# IcosaCharlieCylon.net
KiCad netlist of a schematic drawn in EAGLE
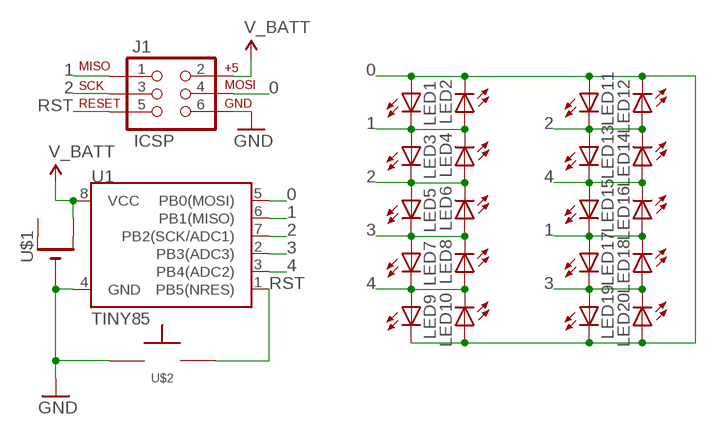
[diagram p0: schematic, sheet 1]

(export (version "E")
  (design (tool "Eeschema 10.0.6"))
  (components
    (comp (ref "J1")
      (value "ICSP")
      (footprint "eagle-import:2X3-NS")
      (libsource (lib "eagle-import") (part "AVR_SPI_PRG_6LABELED"))
    )
    (comp (ref "LED1")
      (value "LEDOVAL")
      (footprint "eagle-import:LED-OVAL")
      (libsource (lib "eagle-import") (part "LEDOVAL"))
    )
    (comp (ref "LED2")
      (value "LEDOVAL")
      (footprint "eagle-import:LED-OVAL")
      (libsource (lib "eagle-import") (part "LEDOVAL"))
    )
    (comp (ref "LED3")
      (value "LEDOVAL")
      (footprint "eagle-import:LED-OVAL")
      (libsource (lib "eagle-import") (part "LEDOVAL"))
    )
    (comp (ref "LED4")
      (value "LEDOVAL")
      (footprint "eagle-import:LED-OVAL")
      (libsource (lib "eagle-import") (part "LEDOVAL"))
    )
    (comp (ref "LED5")
      (value "LEDOVAL")
      (footprint "eagle-import:LED-OVAL")
      (libsource (lib "eagle-import") (part "LEDOVAL"))
    )
    (comp (ref "LED6")
      (value "LEDOVAL")
      (footprint "eagle-import:LED-OVAL")
      (libsource (lib "eagle-import") (part "LEDOVAL"))
    )
    (comp (ref "LED7")
      (value "LEDOVAL")
      (footprint "eagle-import:LED-OVAL")
      (libsource (lib "eagle-import") (part "LEDOVAL"))
    )
    (comp (ref "LED8")
      (value "LEDOVAL")
      (footprint "eagle-import:LED-OVAL")
      (libsource (lib "eagle-import") (part "LEDOVAL"))
    )
    (comp (ref "LED9")
      (value "LEDOVAL")
      (footprint "eagle-import:LED-OVAL")
      (libsource (lib "eagle-import") (part "LEDOVAL"))
    )
    (comp (ref "LED10")
      (value "LEDOVAL")
      (footprint "eagle-import:LED-OVAL")
      (libsource (lib "eagle-import") (part "LEDOVAL"))
    )
    (comp (ref "LED11")
      (value "LEDOVAL")
      (footprint "eagle-import:LED-OVAL")
      (libsource (lib "eagle-import") (part "LEDOVAL"))
    )
    (comp (ref "LED12")
      (value "LEDOVAL")
      (footprint "eagle-import:LED-OVAL")
      (libsource (lib "eagle-import") (part "LEDOVAL"))
    )
    (comp (ref "LED13")
      (value "LEDOVAL")
      (footprint "eagle-import:LED-OVAL")
      (libsource (lib "eagle-import") (part "LEDOVAL"))
    )
    (comp (ref "LED14")
      (value "LEDOVAL")
      (footprint "eagle-import:LED-OVAL")
      (libsource (lib "eagle-import") (part "LEDOVAL"))
    )
    (comp (ref "LED15")
      (value "LEDOVAL")
      (footprint "eagle-import:LED-OVAL")
      (libsource (lib "eagle-import") (part "LEDOVAL"))
    )
    (comp (ref "LED16")
      (value "LEDOVAL")
      (footprint "eagle-import:LED-OVAL")
      (libsource (lib "eagle-import") (part "LEDOVAL"))
    )
    (comp (ref "LED17")
      (value "LEDOVAL")
      (footprint "eagle-import:LED-OVAL")
      (libsource (lib "eagle-import") (part "LEDOVAL"))
    )
    (comp (ref "LED18")
      (value "LEDOVAL")
      (footprint "eagle-import:LED-OVAL")
      (libsource (lib "eagle-import") (part "LEDOVAL"))
    )
    (comp (ref "LED19")
      (value "LEDOVAL")
      (footprint "eagle-import:LED-OVAL")
      (libsource (lib "eagle-import") (part "LEDOVAL"))
    )
    (comp (ref "LED20")
      (value "LEDOVAL")
      (footprint "eagle-import:LED-OVAL")
      (libsource (lib "eagle-import") (part "LEDOVAL"))
    )
    (comp (ref "U$1")
      (value "CR2032THM")
      (footprint "eagle-import:CR2032-THRU")
      (libsource (lib "eagle-import") (part "CR2032THM"))
    )
    (comp (ref "U$2")
      (value "TAC_SPST_NO")
      (footprint "eagle-import:TAC_SPST_NO")
      (libsource (lib "eagle-import") (part "TAC_SPST_NO"))
    )
    (comp (ref "U1")
      (value "TINY85")
      (footprint "eagle-import:DIP08")
      (libsource (lib "eagle-import") (part "ATTINY45TINY85-20-DIP"))
    )
  )
  (nets
    (net (code "1") (name "/0") (class "Default")
      (node (ref "J1") (pin "4") (pinfunction "MOSI_4") (pintype "passive"))
      (node (ref "LED1") (pin "ANODE") (pinfunction "A_ANODE") (pintype "passive"))
      (node (ref "LED10") (pin "ANODE") (pinfunction "A_ANODE") (pintype "passive"))
      (node (ref "LED11") (pin "ANODE") (pinfunction "A_ANODE") (pintype "passive"))
      (node (ref "LED12") (pin "CATHODE") (pinfunction "C_CATHODE") (pintype "passive"))
      (node (ref "LED19") (pin "CATHODE") (pinfunction "C_CATHODE") (pintype "passive"))
      (node (ref "LED2") (pin "CATHODE") (pinfunction "C_CATHODE") (pintype "passive"))
      (node (ref "LED20") (pin "ANODE") (pinfunction "A_ANODE") (pintype "passive"))
      (node (ref "LED9") (pin "CATHODE") (pinfunction "C_CATHODE") (pintype "passive"))
      (node (ref "U1") (pin "5") (pinfunction "PB0(MOSI)_5") (pintype "bidirectional"))
    )
    (net (code "2") (name "/1") (class "Default")
      (node (ref "J1") (pin "1") (pinfunction "MISO_1") (pintype "passive"))
      (node (ref "LED1") (pin "CATHODE") (pinfunction "C_CATHODE") (pintype "passive"))
      (node (ref "LED15") (pin "CATHODE") (pinfunction "C_CATHODE") (pintype "passive"))
      (node (ref "LED16") (pin "ANODE") (pinfunction "A_ANODE") (pintype "passive"))
      (node (ref "LED17") (pin "ANODE") (pinfunction "A_ANODE") (pintype "passive"))
      (node (ref "LED18") (pin "CATHODE") (pinfunction "C_CATHODE") (pintype "passive"))
      (node (ref "LED2") (pin "ANODE") (pinfunction "A_ANODE") (pintype "passive"))
      (node (ref "LED3") (pin "ANODE") (pinfunction "A_ANODE") (pintype "passive"))
      (node (ref "LED4") (pin "CATHODE") (pinfunction "C_CATHODE") (pintype "passive"))
      (node (ref "U1") (pin "6") (pinfunction "PB1(MISO)_6") (pintype "bidirectional"))
    )
    (net (code "3") (name "/2") (class "Default")
      (node (ref "J1") (pin "3") (pinfunction "SCK_3") (pintype "passive"))
      (node (ref "LED11") (pin "CATHODE") (pinfunction "C_CATHODE") (pintype "passive"))
      (node (ref "LED12") (pin "ANODE") (pinfunction "A_ANODE") (pintype "passive"))
      (node (ref "LED13") (pin "ANODE") (pinfunction "A_ANODE") (pintype "passive"))
      (node (ref "LED14") (pin "CATHODE") (pinfunction "C_CATHODE") (pintype "passive"))
      (node (ref "LED3") (pin "CATHODE") (pinfunction "C_CATHODE") (pintype "passive"))
      (node (ref "LED4") (pin "ANODE") (pinfunction "A_ANODE") (pintype "passive"))
      (node (ref "LED5") (pin "ANODE") (pinfunction "A_ANODE") (pintype "passive"))
      (node (ref "LED6") (pin "CATHODE") (pinfunction "C_CATHODE") (pintype "passive"))
      (node (ref "U1") (pin "7") (pinfunction "PB2(SCK/ADC1)_7") (pintype "bidirectional"))
    )
    (net (code "4") (name "/3") (class "Default")
      (node (ref "LED17") (pin "CATHODE") (pinfunction "C_CATHODE") (pintype "passive"))
      (node (ref "LED18") (pin "ANODE") (pinfunction "A_ANODE") (pintype "passive"))
      (node (ref "LED19") (pin "ANODE") (pinfunction "A_ANODE") (pintype "passive"))
      (node (ref "LED20") (pin "CATHODE") (pinfunction "C_CATHODE") (pintype "passive"))
      (node (ref "LED5") (pin "CATHODE") (pinfunction "C_CATHODE") (pintype "passive"))
      (node (ref "LED6") (pin "ANODE") (pinfunction "A_ANODE") (pintype "passive"))
      (node (ref "LED7") (pin "ANODE") (pinfunction "A_ANODE") (pintype "passive"))
      (node (ref "LED8") (pin "CATHODE") (pinfunction "C_CATHODE") (pintype "passive"))
      (node (ref "U1") (pin "2") (pinfunction "PB3(ADC3)_2") (pintype "bidirectional"))
    )
    (net (code "5") (name "/4") (class "Default")
      (node (ref "LED10") (pin "CATHODE") (pinfunction "C_CATHODE") (pintype "passive"))
      (node (ref "LED13") (pin "CATHODE") (pinfunction "C_CATHODE") (pintype "passive"))
      (node (ref "LED14") (pin "ANODE") (pinfunction "A_ANODE") (pintype "passive"))
      (node (ref "LED15") (pin "ANODE") (pinfunction "A_ANODE") (pintype "passive"))
      (node (ref "LED16") (pin "CATHODE") (pinfunction "C_CATHODE") (pintype "passive"))
      (node (ref "LED7") (pin "CATHODE") (pinfunction "C_CATHODE") (pintype "passive"))
      (node (ref "LED8") (pin "ANODE") (pinfunction "A_ANODE") (pintype "passive"))
      (node (ref "LED9") (pin "ANODE") (pinfunction "A_ANODE") (pintype "passive"))
      (node (ref "U1") (pin "3") (pinfunction "PB4(ADC2)_3") (pintype "bidirectional"))
    )
    (net (code "6") (name "/RST") (class "Default")
      (node (ref "J1") (pin "5") (pinfunction "RST_5") (pintype "passive"))
      (node (ref "U$2") (pin "P$2") (pinfunction "P$2_P$2") (pintype "bidirectional"))
      (node (ref "U1") (pin "1") (pinfunction "PB5(NRES)_1") (pintype "bidirectional"))
    )
    (net (code "7") (name "GND") (class "Default")
      (node (ref "J1") (pin "6") (pinfunction "GND_6") (pintype "passive"))
      (node (ref "U$1") (pin "-") (pinfunction "-_-") (pintype "passive"))
      (node (ref "U$2") (pin "P$1") (pinfunction "P$1_P$1") (pintype "bidirectional"))
      (node (ref "U1") (pin "4") (pinfunction "GND_4") (pintype "bidirectional"))
    )
    (net (code "8") (name "V_BATT") (class "Default")
      (node (ref "J1") (pin "2") (pinfunction "V+_2") (pintype "passive"))
      (node (ref "U$1") (pin "+2") (pinfunction "+1_+2") (pintype "passive"))
      (node (ref "U1") (pin "8") (pinfunction "VCC_8") (pintype "bidirectional"))
    )
    (net (code "9") (name "unconnected-(U$1-+-Pad+1)") (class "Default")
      (node (ref "U$1") (pin "+1") (pinfunction "+_+1") (pintype "passive"))
    )
  )
)
